# NotNightVision_r001.net
KiCad netlist of a schematic drawn in EAGLE
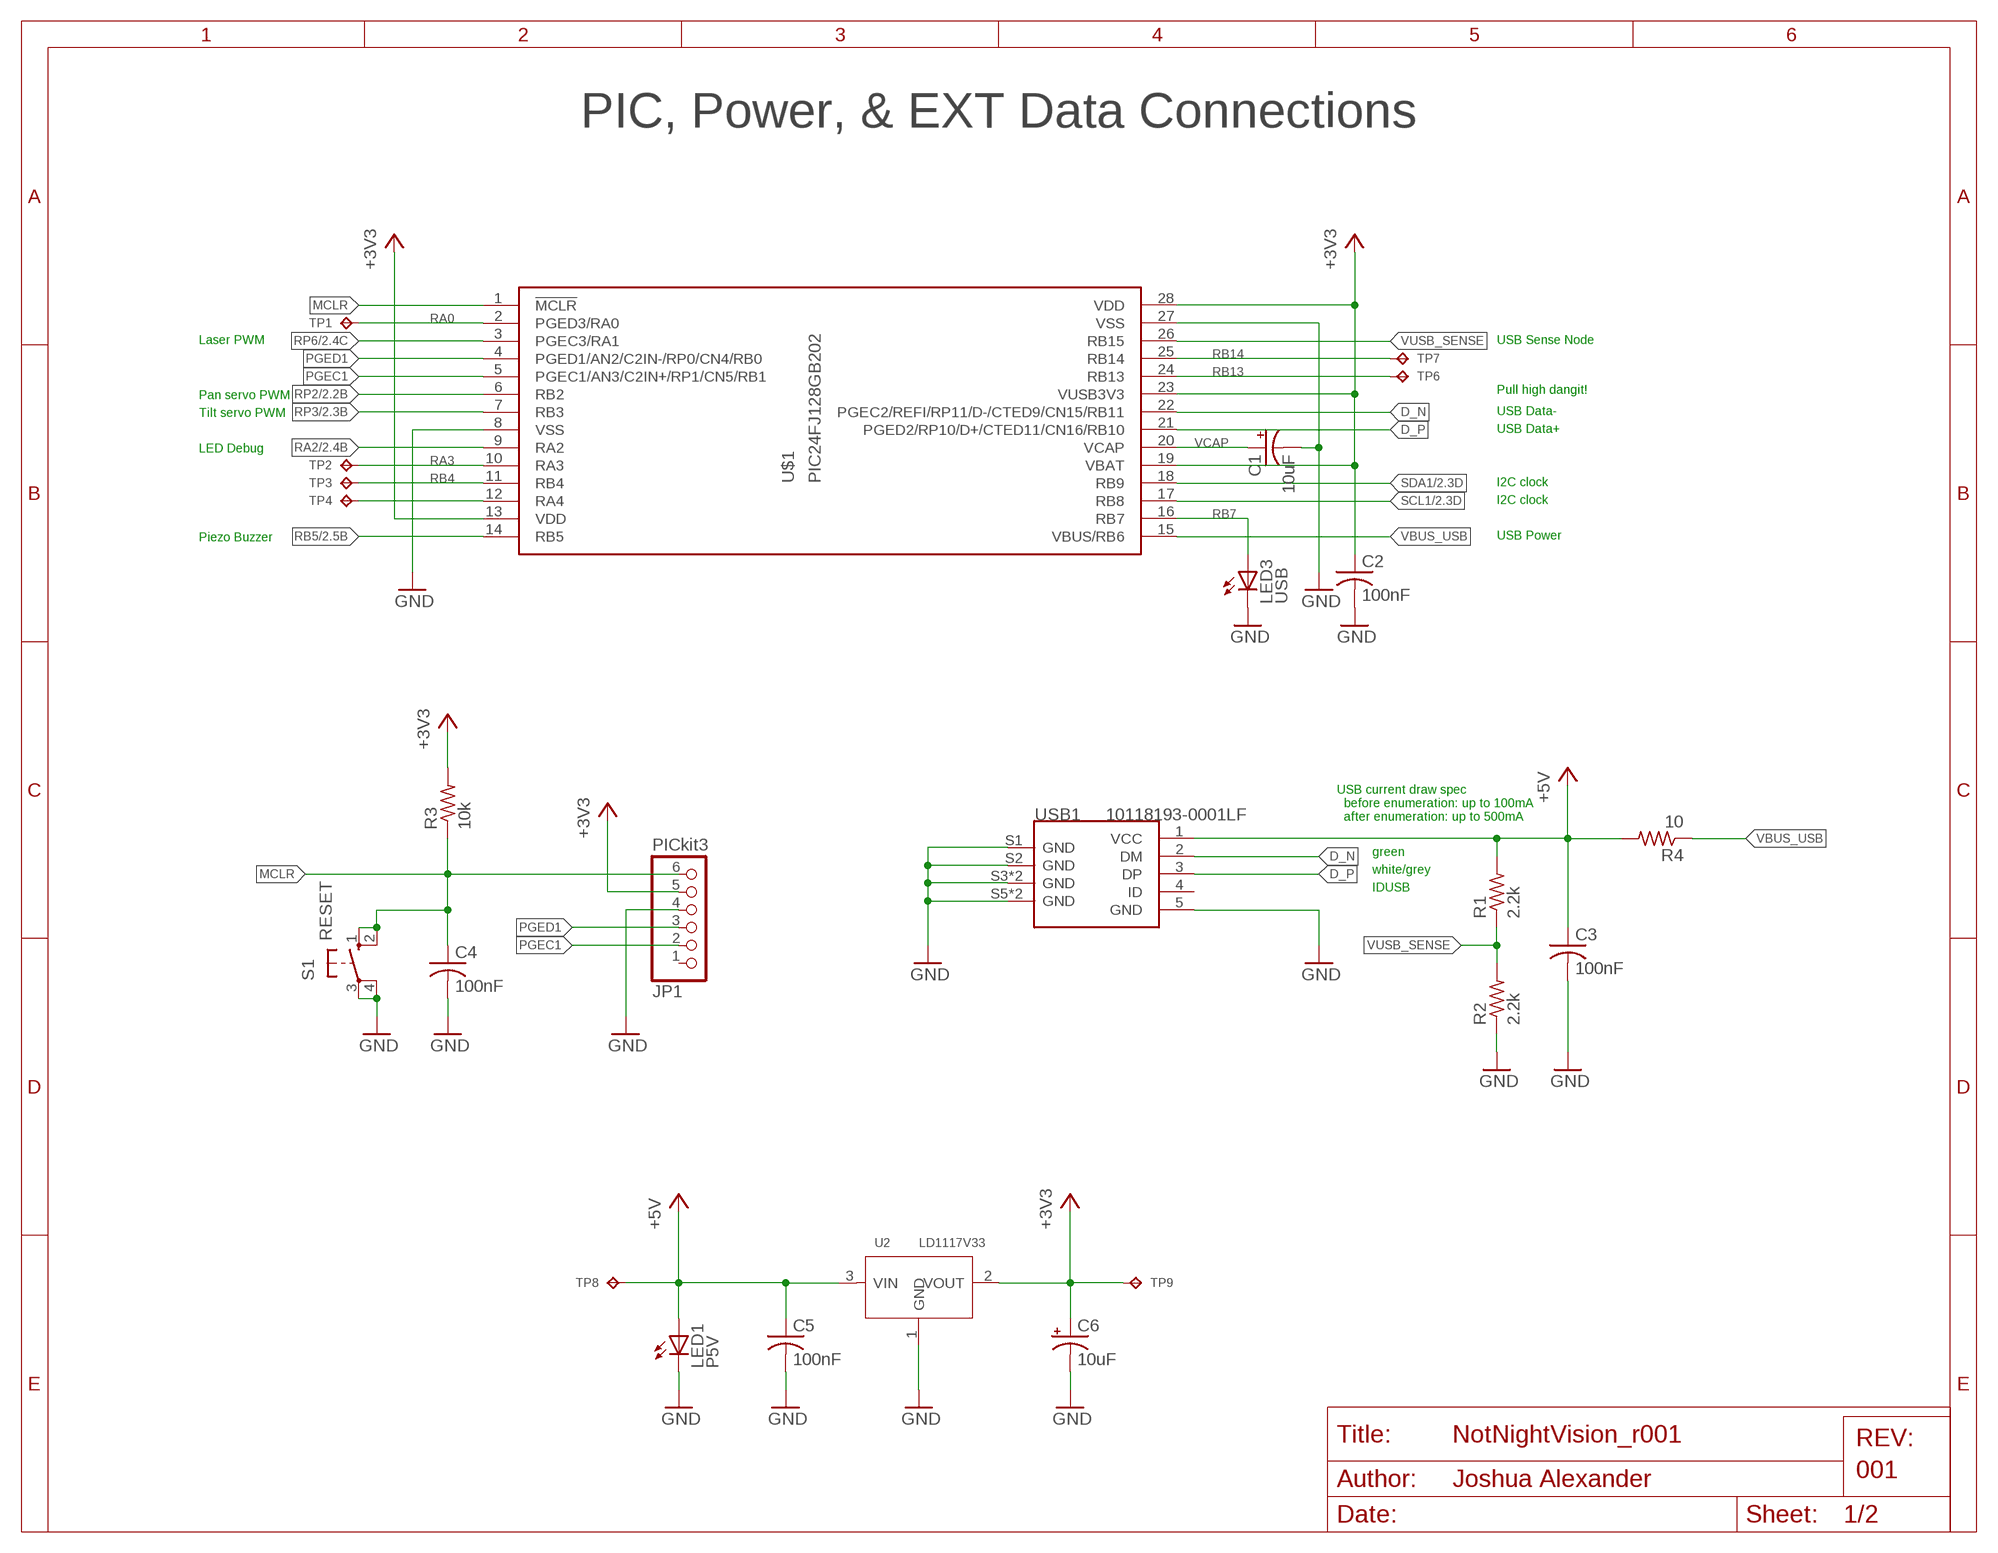
[diagram p0: schematic, sheet 1]
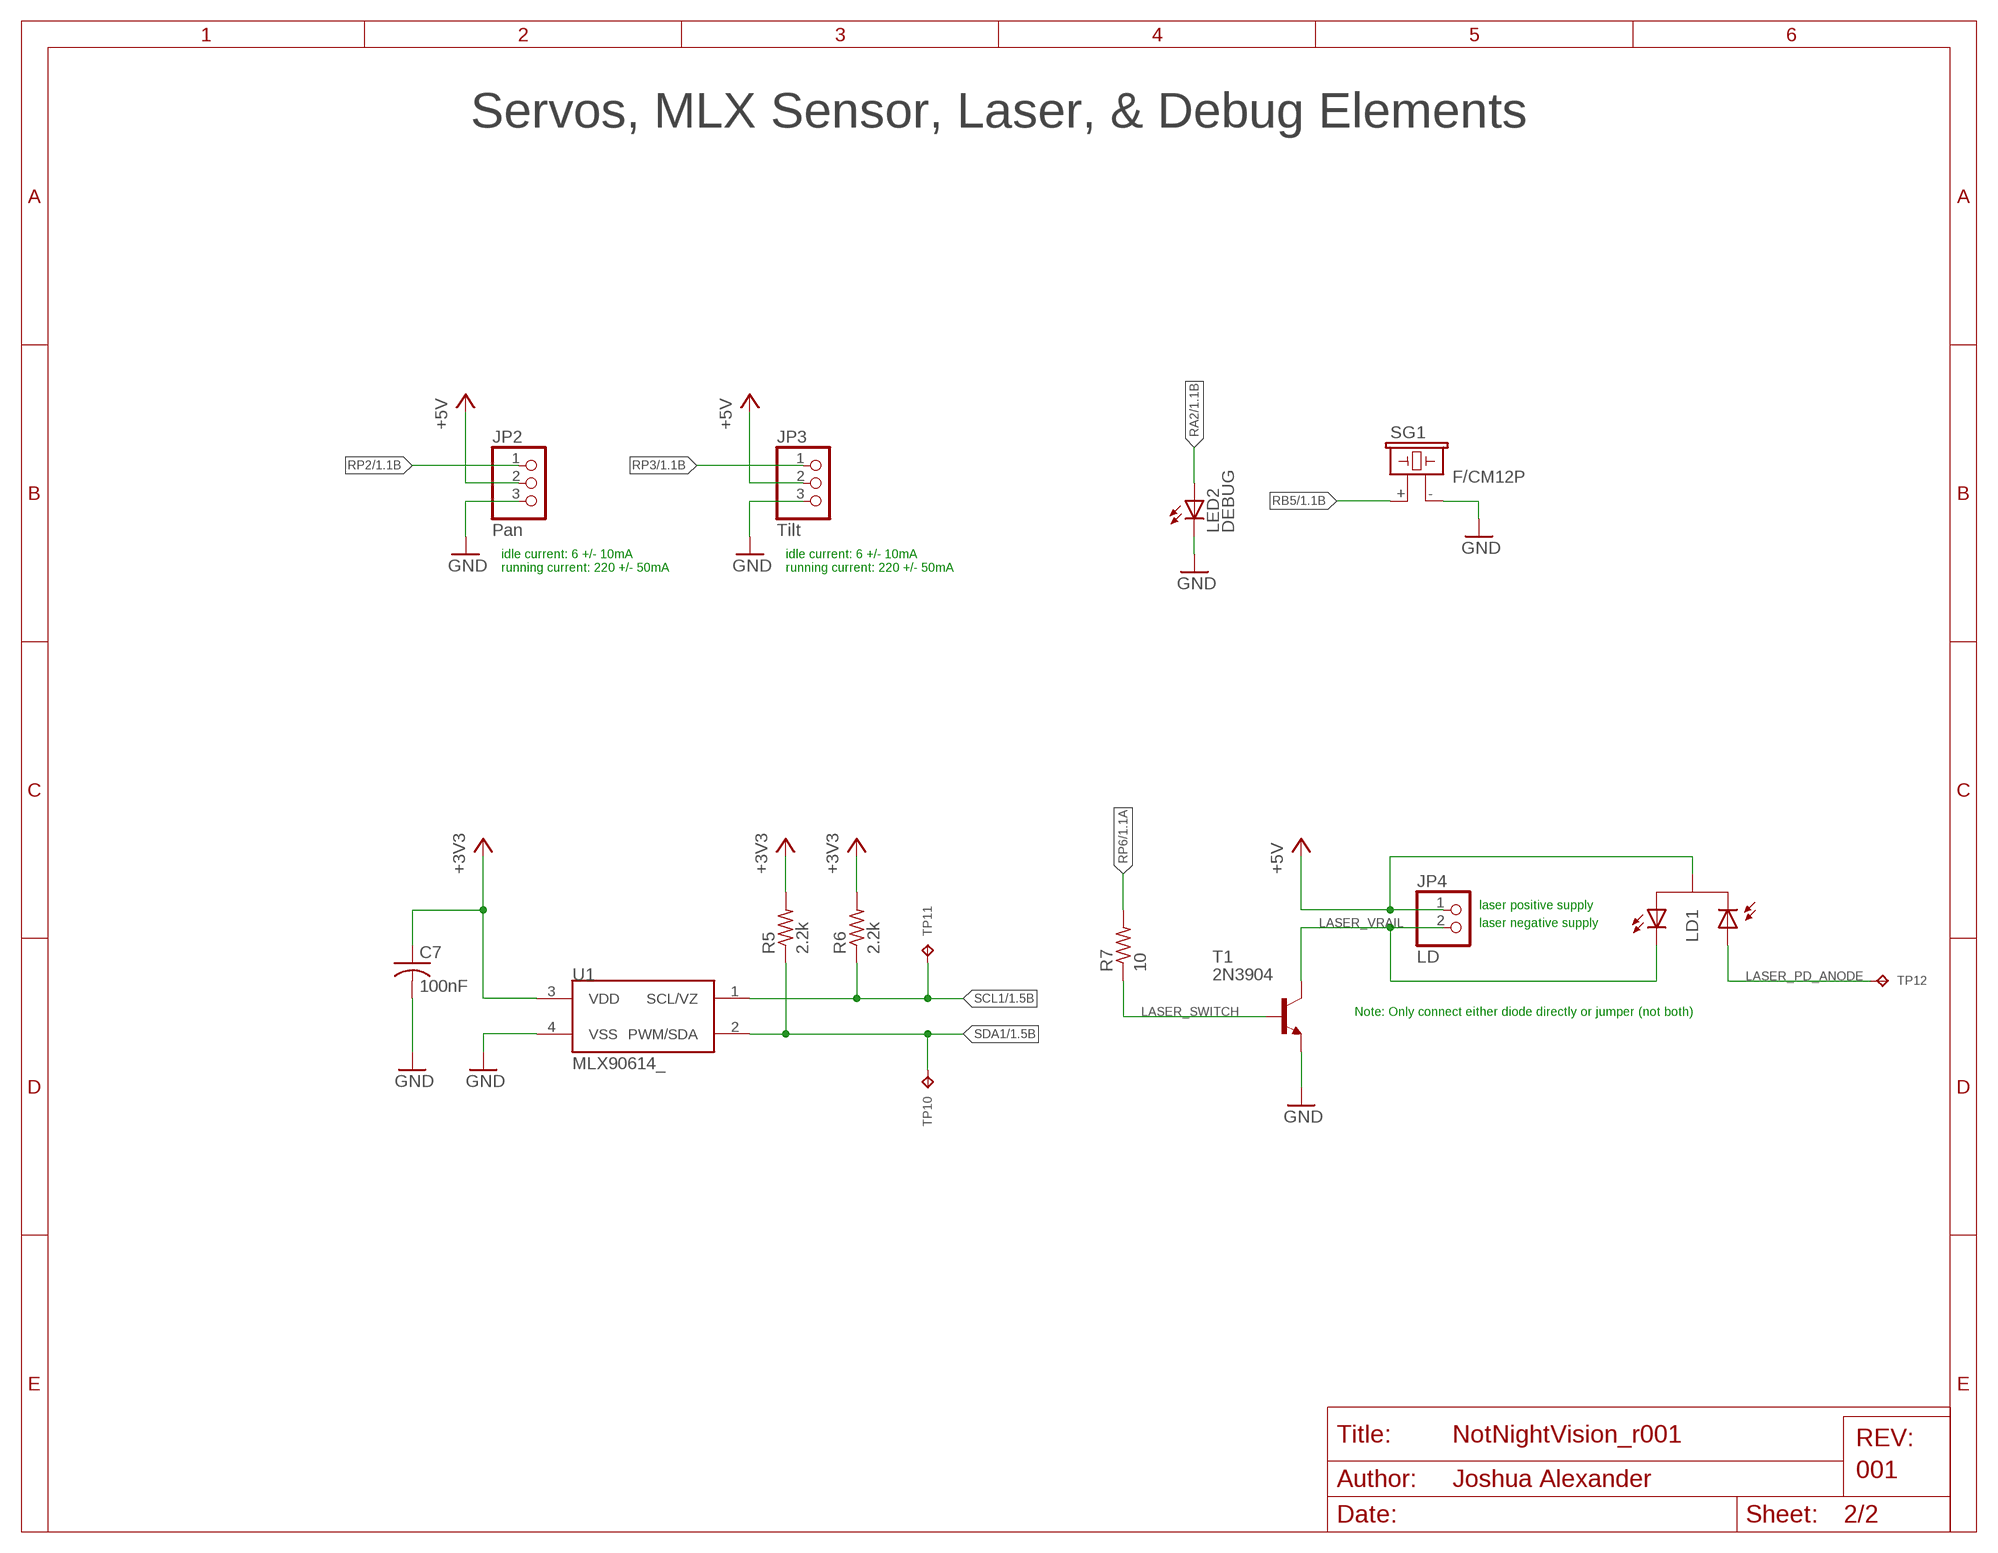
[diagram p1: schematic, sheet 2]

(export (version "E")
  (design (tool "Eeschema 10.0.6"))
  (components
    (comp (ref "C7")
      (value "100nF")
      (footprint "eagle-import:C025-025X050")
      (libsource (lib "eagle-import") (part "C-US025-025X050"))
    )
    (comp (ref "JP2")
      (value "Pan")
      (footprint "eagle-import:1X03")
      (libsource (lib "eagle-import") (part "PINHD-1X3"))
    )
    (comp (ref "JP3")
      (value "Tilt")
      (footprint "eagle-import:1X03")
      (libsource (lib "eagle-import") (part "PINHD-1X3"))
    )
    (comp (ref "JP4")
      (value "LD")
      (footprint "eagle-import:1X02")
      (libsource (lib "eagle-import") (part "PINHD-1X2"))
    )
    (comp (ref "LD1")
      (value "LASER_DIODE")
      (footprint "eagle-import:TO-18")
      (libsource (lib "eagle-import") (part "LASER_DIODE"))
    )
    (comp (ref "LED2")
      (value "DEBUG")
      (footprint "eagle-import:LED3MM")
      (libsource (lib "eagle-import") (part "LED3MM"))
    )
    (comp (ref "R5")
      (value "2.2k")
      (footprint "eagle-import:0207_7")
      (libsource (lib "eagle-import") (part "R-US_0207/7"))
    )
    (comp (ref "R6")
      (value "2.2k")
      (footprint "eagle-import:0207_7")
      (libsource (lib "eagle-import") (part "R-US_0207/7"))
    )
    (comp (ref "R7")
      (value "10")
      (footprint "eagle-import:0207_7")
      (libsource (lib "eagle-import") (part "R-US_0207/7"))
    )
    (comp (ref "SG1")
      (value "F/CM12P")
      (footprint "eagle-import:F_CM12P")
      (libsource (lib "eagle-import") (part "F/CM12P"))
    )
    (comp (ref "T1")
      (value "2N3904")
      (footprint "eagle-import:TO92")
      (libsource (lib "eagle-import") (part "2N3904"))
    )
    (comp (ref "TP10")
      (value "TP10")
      (footprint "eagle-import:10MIL_ROUND")
      (libsource (lib "eagle-import") (part "TP10"))
    )
    (comp (ref "TP11")
      (value "TP10")
      (footprint "eagle-import:10MIL_ROUND")
      (libsource (lib "eagle-import") (part "TP10"))
    )
    (comp (ref "TP12")
      (value "TP10")
      (footprint "eagle-import:10MIL_ROUND")
      (libsource (lib "eagle-import") (part "TP10"))
    )
    (comp (ref "U1")
      (value "MLX90614_")
      (footprint "eagle-import:TO-39")
      (fields (field (name "MPN") "1747"))
      (libsource (lib "eagle-import") (part "MLX90614_"))
    )
    (comp (ref "C1")
      (value "10uF")
      (footprint "eagle-import:TT5D10")
      (libsource (lib "eagle-import") (part "CPOL-USTT5D10"))
    )
    (comp (ref "C2")
      (value "100nF")
      (footprint "eagle-import:C025-025X050")
      (libsource (lib "eagle-import") (part "C-US025-025X050"))
    )
    (comp (ref "C3")
      (value "100nF")
      (footprint "eagle-import:C025-025X050")
      (libsource (lib "eagle-import") (part "C-US025-025X050"))
    )
    (comp (ref "C4")
      (value "100nF")
      (footprint "eagle-import:C025-025X050")
      (libsource (lib "eagle-import") (part "C-US025-025X050"))
    )
    (comp (ref "C5")
      (value "100nF")
      (footprint "eagle-import:C025-025X050")
      (libsource (lib "eagle-import") (part "C-US025-025X050"))
    )
    (comp (ref "C6")
      (value "10uF")
      (footprint "eagle-import:TT5D10")
      (libsource (lib "eagle-import") (part "CPOL-USTT5D10"))
    )
    (comp (ref "JP1")
      (value "PICkit3")
      (footprint "eagle-import:1X06_90")
      (libsource (lib "eagle-import") (part "PINHD-1X6/90"))
    )
    (comp (ref "LED1")
      (value "P5V")
      (footprint "eagle-import:LED5MM")
      (libsource (lib "eagle-import") (part "LED5MM"))
    )
    (comp (ref "LED3")
      (value "USB")
      (footprint "eagle-import:LED3MM")
      (libsource (lib "eagle-import") (part "LED3MM"))
    )
    (comp (ref "R1")
      (value "2.2k")
      (footprint "eagle-import:0207_7")
      (libsource (lib "eagle-import") (part "R-US_0207/7"))
    )
    (comp (ref "R2")
      (value "2.2k")
      (footprint "eagle-import:0207_7")
      (libsource (lib "eagle-import") (part "R-US_0207/7"))
    )
    (comp (ref "R3")
      (value "10k")
      (footprint "eagle-import:0207_7")
      (libsource (lib "eagle-import") (part "R-US_0207/7"))
    )
    (comp (ref "R4")
      (value "10")
      (footprint "eagle-import:0207_7")
      (libsource (lib "eagle-import") (part "R-US_0207/7"))
    )
    (comp (ref "S1")
      (value "RESET")
      (footprint "eagle-import:B3F-10XX")
      (fields (field (name "MPN") "B3F-1000"))
      (libsource (lib "eagle-import") (part "10-XX"))
    )
    (comp (ref "TP1")
      (value "TP10")
      (footprint "eagle-import:10MIL_ROUND")
      (libsource (lib "eagle-import") (part "TP10"))
    )
    (comp (ref "TP2")
      (value "TP10")
      (footprint "eagle-import:10MIL_ROUND")
      (libsource (lib "eagle-import") (part "TP10"))
    )
    (comp (ref "TP3")
      (value "TP10")
      (footprint "eagle-import:10MIL_ROUND")
      (libsource (lib "eagle-import") (part "TP10"))
    )
    (comp (ref "TP4")
      (value "TP10")
      (footprint "eagle-import:10MIL_ROUND")
      (libsource (lib "eagle-import") (part "TP10"))
    )
    (comp (ref "TP6")
      (value "TP10")
      (footprint "eagle-import:10MIL_ROUND")
      (libsource (lib "eagle-import") (part "TP10"))
    )
    (comp (ref "TP7")
      (value "TP10")
      (footprint "eagle-import:10MIL_ROUND")
      (libsource (lib "eagle-import") (part "TP10"))
    )
    (comp (ref "TP8")
      (value "TP10")
      (footprint "eagle-import:10MIL_ROUND")
      (libsource (lib "eagle-import") (part "TP10"))
    )
    (comp (ref "TP9")
      (value "TP10")
      (footprint "eagle-import:10MIL_ROUND")
      (libsource (lib "eagle-import") (part "TP10"))
    )
    (comp (ref "U$1")
      (value "PIC24FJ128GB202")
      (footprint "eagle-import:DIL28-3")
      (libsource (lib "eagle-import") (part "PIC24FJ128GB202"))
    )
    (comp (ref "U2")
      (value "LD1117V33")
      (footprint "eagle-import:TO-220V")
      (libsource (lib "eagle-import") (part "LD1117V33TO220V"))
    )
    (comp (ref "USB1")
      (value "10118193-0001LF")
      (footprint "eagle-import:MICRO-USB5+6P-SMD-0.65-B")
      (libsource (lib "eagle-import") (part "MICRO-USB-SMD-B-(10118193-0001LF)"))
    )
  )
  (nets
    (net (code "1") (name "+3V3") (class "Default")
      (node (ref "C2") (pin "1") (pinfunction "1_1") (pintype "passive"))
      (node (ref "C6") (pin "+") (pinfunction "+_+") (pintype "passive"))
      (node (ref "C7") (pin "1") (pinfunction "1_1") (pintype "passive"))
      (node (ref "JP1") (pin "5") (pinfunction "5_5") (pintype "passive"))
      (node (ref "R3") (pin "2") (pinfunction "2_2") (pintype "passive"))
      (node (ref "R5") (pin "2") (pinfunction "2_2") (pintype "passive"))
      (node (ref "R6") (pin "2") (pinfunction "2_2") (pintype "passive"))
      (node (ref "TP9") (pin "TP") (pinfunction "TP_TP") (pintype "input"))
      (node (ref "U$1") (pin "13") (pinfunction "VDD_13") (pintype "power_in"))
      (node (ref "U$1") (pin "19") (pinfunction "VBAT_19") (pintype "power_in"))
      (node (ref "U$1") (pin "23") (pinfunction "VUSB3V3_23") (pintype "bidirectional"))
      (node (ref "U$1") (pin "28") (pinfunction "VDD_28") (pintype "power_in"))
      (node (ref "U1") (pin "3") (pinfunction "VDD_3") (pintype "bidirectional"))
      (node (ref "U2") (pin "2") (pinfunction "VOUT_2") (pintype "bidirectional"))
    )
    (net (code "2") (name "+5V") (class "Default")
      (node (ref "C3") (pin "1") (pinfunction "1_1") (pintype "passive"))
      (node (ref "C5") (pin "1") (pinfunction "1_1") (pintype "passive"))
      (node (ref "JP2") (pin "2") (pinfunction "2_2") (pintype "passive"))
      (node (ref "JP3") (pin "2") (pinfunction "2_2") (pintype "passive"))
      (node (ref "JP4") (pin "1") (pinfunction "1_1") (pintype "passive"))
      (node (ref "LD1") (pin "2") (pinfunction "V_2") (pintype "passive"))
      (node (ref "LED1") (pin "A") (pinfunction "A_A") (pintype "passive"))
      (node (ref "R1") (pin "2") (pinfunction "2_2") (pintype "passive"))
      (node (ref "R4") (pin "2") (pinfunction "2_2") (pintype "passive"))
      (node (ref "TP8") (pin "TP") (pinfunction "TP_TP") (pintype "input"))
      (node (ref "U2") (pin "3") (pinfunction "VIN_3") (pintype "bidirectional"))
      (node (ref "USB1") (pin "1") (pinfunction "VCC_1") (pintype "bidirectional"))
    )
    (net (code "3") (name "D_N") (class "Default")
      (node (ref "U$1") (pin "22") (pinfunction "PGEC2/REFI/RP11/D-/CTED9/CN15/RB11_22") (pintype "bidirectional"))
      (node (ref "USB1") (pin "2") (pinfunction "DM_2") (pintype "bidirectional"))
    )
    (net (code "4") (name "D_P") (class "Default")
      (node (ref "U$1") (pin "21") (pinfunction "PGED2/RP10/D+/CTED11/CN16/RB10_21") (pintype "bidirectional"))
      (node (ref "USB1") (pin "3") (pinfunction "DP_3") (pintype "bidirectional"))
    )
    (net (code "5") (name "GND") (class "Default")
      (node (ref "C1") (pin "-") (pinfunction "-_-") (pintype "passive"))
      (node (ref "C2") (pin "2") (pinfunction "2_2") (pintype "passive"))
      (node (ref "C3") (pin "2") (pinfunction "2_2") (pintype "passive"))
      (node (ref "C4") (pin "2") (pinfunction "2_2") (pintype "passive"))
      (node (ref "C5") (pin "2") (pinfunction "2_2") (pintype "passive"))
      (node (ref "C6") (pin "-") (pinfunction "-_-") (pintype "passive"))
      (node (ref "C7") (pin "2") (pinfunction "2_2") (pintype "passive"))
      (node (ref "JP1") (pin "4") (pinfunction "4_4") (pintype "passive"))
      (node (ref "JP2") (pin "3") (pinfunction "3_3") (pintype "passive"))
      (node (ref "JP3") (pin "3") (pinfunction "3_3") (pintype "passive"))
      (node (ref "LED1") (pin "K") (pinfunction "C_K") (pintype "passive"))
      (node (ref "LED2") (pin "K") (pinfunction "C_K") (pintype "passive"))
      (node (ref "LED3") (pin "K") (pinfunction "C_K") (pintype "passive"))
      (node (ref "R2") (pin "1") (pinfunction "1_1") (pintype "passive"))
      (node (ref "S1") (pin "3") (pinfunction "P_3") (pintype "passive"))
      (node (ref "S1") (pin "4") (pinfunction "P1_4") (pintype "passive"))
      (node (ref "SG1") (pin "-") (pinfunction "2_-") (pintype "passive"))
      (node (ref "T1") (pin "3") (pinfunction "E_3") (pintype "passive"))
      (node (ref "U$1") (pin "27") (pinfunction "VSS_27") (pintype "power_in"))
      (node (ref "U$1") (pin "8") (pinfunction "VSS_8") (pintype "power_in"))
      (node (ref "U1") (pin "4") (pinfunction "VSS_4") (pintype "bidirectional"))
      (node (ref "U2") (pin "1") (pinfunction "GND_1") (pintype "bidirectional"))
      (node (ref "USB1") (pin "5") (pinfunction "GND_5") (pintype "bidirectional"))
      (node (ref "USB1") (pin "S1") (pinfunction "GND_S1") (pintype "bidirectional"))
      (node (ref "USB1") (pin "S2") (pinfunction "GND_S2") (pintype "bidirectional"))
      (node (ref "USB1") (pin "S3") (pinfunction "GND_S3") (pintype "bidirectional"))
      (node (ref "USB1") (pin "S4") (pinfunction "GND_S4") (pintype "bidirectional"))
      (node (ref "USB1") (pin "S5") (pinfunction "GND_S5") (pintype "bidirectional"))
      (node (ref "USB1") (pin "S6") (pinfunction "GND_S6") (pintype "bidirectional"))
    )
    (net (code "6") (name "LASER_PD_ANODE") (class "Default")
      (node (ref "LD1") (pin "3") (pinfunction "D+_3") (pintype "passive"))
      (node (ref "TP12") (pin "TP") (pinfunction "TP_TP") (pintype "input"))
    )
    (net (code "7") (name "LASER_SWITCH") (class "Default")
      (node (ref "R7") (pin "1") (pinfunction "1_1") (pintype "passive"))
      (node (ref "T1") (pin "2") (pinfunction "B_2") (pintype "passive"))
    )
    (net (code "8") (name "LASER_VRAIL") (class "Default")
      (node (ref "JP4") (pin "2") (pinfunction "2_2") (pintype "passive"))
      (node (ref "LD1") (pin "1") (pinfunction "D-_1") (pintype "passive"))
      (node (ref "T1") (pin "1") (pinfunction "C_1") (pintype "passive"))
    )
    (net (code "9") (name "MCLR") (class "Default")
      (node (ref "C4") (pin "1") (pinfunction "1_1") (pintype "passive"))
      (node (ref "JP1") (pin "6") (pinfunction "6_6") (pintype "passive"))
      (node (ref "R3") (pin "1") (pinfunction "1_1") (pintype "passive"))
      (node (ref "S1") (pin "1") (pinfunction "S_1") (pintype "passive"))
      (node (ref "S1") (pin "2") (pinfunction "S1_2") (pintype "passive"))
      (node (ref "U$1") (pin "1") (pinfunction "~{MCLR}_1") (pintype "bidirectional"))
    )
    (net (code "10") (name "Net-(U$1-RA4)") (class "Default")
      (node (ref "TP4") (pin "TP") (pinfunction "TP_TP") (pintype "input"))
      (node (ref "U$1") (pin "12") (pinfunction "RA4_12") (pintype "bidirectional"))
    )
    (net (code "11") (name "PGEC1") (class "Default")
      (node (ref "JP1") (pin "2") (pinfunction "2_2") (pintype "passive"))
      (node (ref "U$1") (pin "5") (pinfunction "PGEC1/AN3/C2IN+/RP1/CN5/RB1_5") (pintype "bidirectional"))
    )
    (net (code "12") (name "PGED1") (class "Default")
      (node (ref "JP1") (pin "3") (pinfunction "3_3") (pintype "passive"))
      (node (ref "U$1") (pin "4") (pinfunction "PGED1/AN2/C2IN-/RP0/CN4/RB0_4") (pintype "bidirectional"))
    )
    (net (code "13") (name "RA0") (class "Default")
      (node (ref "TP1") (pin "TP") (pinfunction "TP_TP") (pintype "input"))
      (node (ref "U$1") (pin "2") (pinfunction "PGED3/RA0_2") (pintype "bidirectional"))
    )
    (net (code "14") (name "RA2") (class "Default")
      (node (ref "LED2") (pin "A") (pinfunction "A_A") (pintype "passive"))
      (node (ref "U$1") (pin "9") (pinfunction "RA2_9") (pintype "bidirectional"))
    )
    (net (code "15") (name "RA3") (class "Default")
      (node (ref "TP2") (pin "TP") (pinfunction "TP_TP") (pintype "input"))
      (node (ref "U$1") (pin "10") (pinfunction "RA3_10") (pintype "bidirectional"))
    )
    (net (code "16") (name "RB4") (class "Default")
      (node (ref "TP3") (pin "TP") (pinfunction "TP_TP") (pintype "input"))
      (node (ref "U$1") (pin "11") (pinfunction "RB4_11") (pintype "bidirectional"))
    )
    (net (code "17") (name "RB5") (class "Default")
      (node (ref "SG1") (pin "+") (pinfunction "1_+") (pintype "passive"))
      (node (ref "U$1") (pin "14") (pinfunction "RB5_14") (pintype "bidirectional"))
    )
    (net (code "18") (name "RB7") (class "Default")
      (node (ref "LED3") (pin "A") (pinfunction "A_A") (pintype "passive"))
      (node (ref "U$1") (pin "16") (pinfunction "RB7_16") (pintype "bidirectional"))
    )
    (net (code "19") (name "RB13") (class "Default")
      (node (ref "TP6") (pin "TP") (pinfunction "TP_TP") (pintype "input"))
      (node (ref "U$1") (pin "24") (pinfunction "RB13_24") (pintype "bidirectional"))
    )
    (net (code "20") (name "RB14") (class "Default")
      (node (ref "TP7") (pin "TP") (pinfunction "TP_TP") (pintype "input"))
      (node (ref "U$1") (pin "25") (pinfunction "RB14_25") (pintype "bidirectional"))
    )
    (net (code "21") (name "RP2") (class "Default")
      (node (ref "JP2") (pin "1") (pinfunction "1_1") (pintype "passive"))
      (node (ref "U$1") (pin "6") (pinfunction "RB2_6") (pintype "bidirectional"))
    )
    (net (code "22") (name "RP3") (class "Default")
      (node (ref "JP3") (pin "1") (pinfunction "1_1") (pintype "passive"))
      (node (ref "U$1") (pin "7") (pinfunction "RB3_7") (pintype "bidirectional"))
    )
    (net (code "23") (name "RP6") (class "Default")
      (node (ref "R7") (pin "2") (pinfunction "2_2") (pintype "passive"))
      (node (ref "U$1") (pin "3") (pinfunction "PGEC3/RA1_3") (pintype "bidirectional"))
    )
    (net (code "24") (name "SCL1") (class "Default")
      (node (ref "R6") (pin "1") (pinfunction "1_1") (pintype "passive"))
      (node (ref "TP11") (pin "TP") (pinfunction "TP_TP") (pintype "input"))
      (node (ref "U$1") (pin "17") (pinfunction "RB8_17") (pintype "bidirectional"))
      (node (ref "U1") (pin "1") (pinfunction "SCL/VZ_1") (pintype "bidirectional"))
    )
    (net (code "25") (name "SDA1") (class "Default")
      (node (ref "R5") (pin "1") (pinfunction "1_1") (pintype "passive"))
      (node (ref "TP10") (pin "TP") (pinfunction "TP_TP") (pintype "input"))
      (node (ref "U$1") (pin "18") (pinfunction "RB9_18") (pintype "bidirectional"))
      (node (ref "U1") (pin "2") (pinfunction "PWM/SDA_2") (pintype "bidirectional"))
    )
    (net (code "26") (name "VBUS_USB") (class "Default")
      (node (ref "R4") (pin "1") (pinfunction "1_1") (pintype "passive"))
      (node (ref "U$1") (pin "15") (pinfunction "VBUS/RB6_15") (pintype "power_in"))
    )
    (net (code "27") (name "VCAP") (class "Default")
      (node (ref "C1") (pin "+") (pinfunction "+_+") (pintype "passive"))
      (node (ref "U$1") (pin "20") (pinfunction "VCAP_20") (pintype "passive"))
    )
    (net (code "28") (name "VUSB_SENSE") (class "Default")
      (node (ref "R1") (pin "1") (pinfunction "1_1") (pintype "passive"))
      (node (ref "R2") (pin "2") (pinfunction "2_2") (pintype "passive"))
      (node (ref "U$1") (pin "26") (pinfunction "RB15_26") (pintype "bidirectional"))
    )
    (net (code "29") (name "unconnected-(JP1-Pad1)") (class "Default")
      (node (ref "JP1") (pin "1") (pinfunction "1_1") (pintype "passive"))
    )
    (net (code "30") (name "unconnected-(USB1-ID-Pad4)") (class "Default")
      (node (ref "USB1") (pin "4") (pinfunction "ID_4") (pintype "bidirectional"))
    )
  )
)
